# motor_driver_irf7413.net
KiCad netlist of a schematic drawn in EAGLE
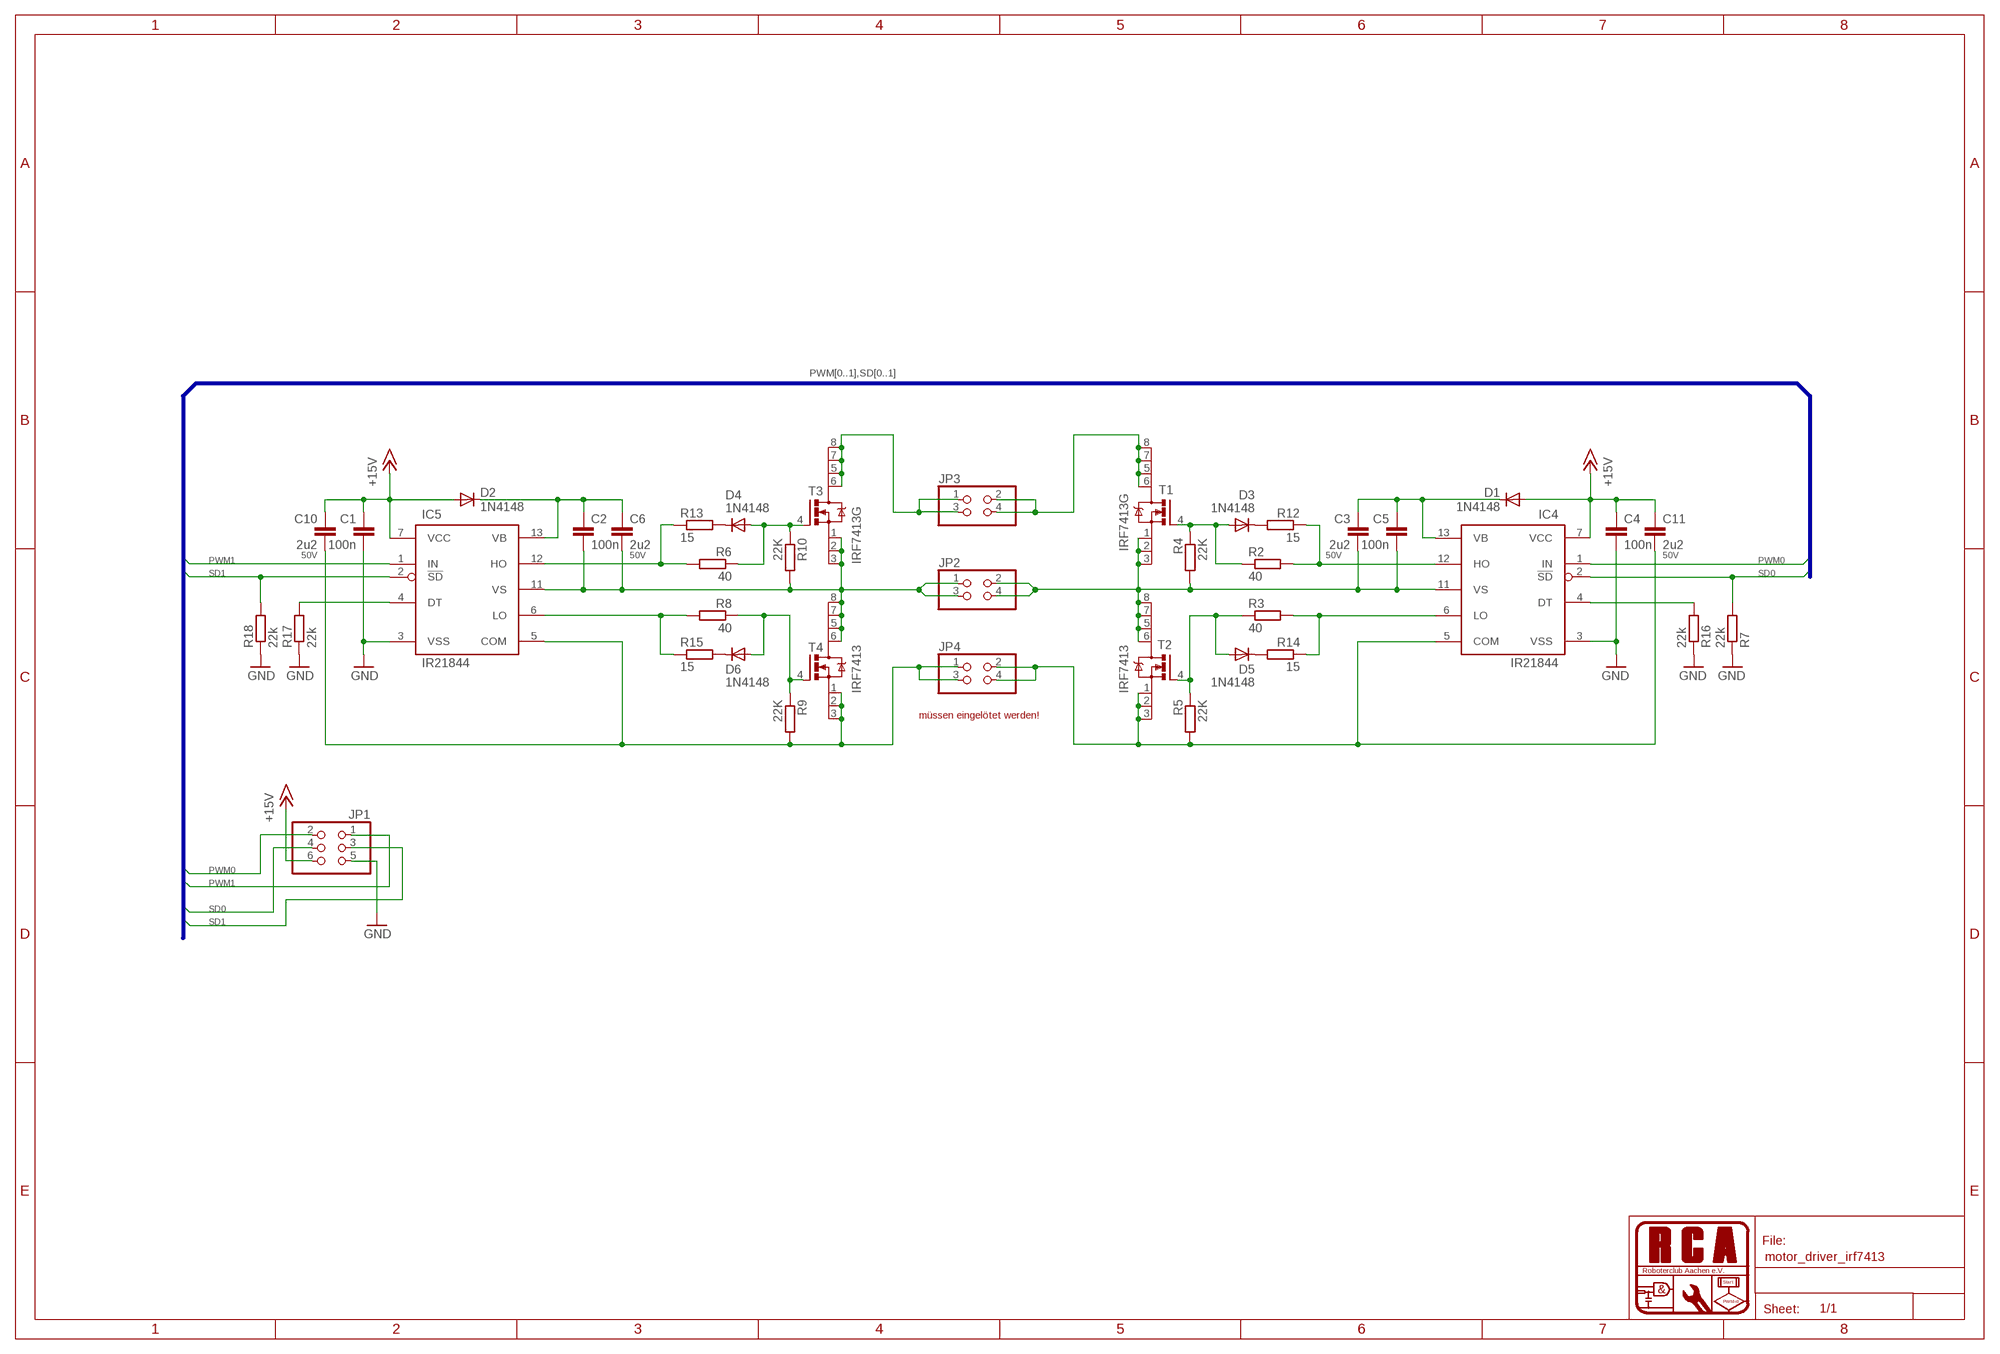
[diagram p0: schematic, sheet 1]

(export (version "E")
  (design (tool "Eeschema 10.0.6"))
  (components
    (comp (ref "C1")
      (value "100n")
      (footprint "eagle-import:C0805")
      (libsource (lib "eagle-import") (part "C-EUC0805"))
    )
    (comp (ref "C2")
      (value "100n")
      (footprint "eagle-import:C1206")
      (libsource (lib "eagle-import") (part "C-EUC1206"))
    )
    (comp (ref "C3")
      (value "2u2")
      (footprint "eagle-import:C1206")
      (fields (field (name "VOLTAGE") "50V"))
      (libsource (lib "eagle-import") (part "C-EUC1206"))
    )
    (comp (ref "C4")
      (value "100n")
      (footprint "eagle-import:C0805")
      (libsource (lib "eagle-import") (part "C-EUC0805"))
    )
    (comp (ref "C5")
      (value "100n")
      (footprint "eagle-import:C1206")
      (libsource (lib "eagle-import") (part "C-EUC1206"))
    )
    (comp (ref "C6")
      (value "2u2")
      (footprint "eagle-import:C1206")
      (fields (field (name "VOLTAGE") "50V"))
      (libsource (lib "eagle-import") (part "C-EUC1206"))
    )
    (comp (ref "C10")
      (value "2u2")
      (footprint "eagle-import:C1206")
      (fields (field (name "VOLTAGE") "50V"))
      (libsource (lib "eagle-import") (part "C-EUC1206"))
    )
    (comp (ref "C11")
      (value "2u2")
      (footprint "eagle-import:C1206")
      (fields (field (name "VOLTAGE") "50V"))
      (libsource (lib "eagle-import") (part "C-EUC1206"))
    )
    (comp (ref "D1")
      (value "1N4148")
      (footprint "eagle-import:SOD80C")
      (libsource (lib "eagle-import") (part "DIODE-SOD80C"))
    )
    (comp (ref "D2")
      (value "1N4148")
      (footprint "eagle-import:SOD80C")
      (libsource (lib "eagle-import") (part "DIODE-SOD80C"))
    )
    (comp (ref "D3")
      (value "1N4148")
      (footprint "eagle-import:SOD80C")
      (libsource (lib "eagle-import") (part "DIODE-SOD80C"))
    )
    (comp (ref "D4")
      (value "1N4148")
      (footprint "eagle-import:SOD80C")
      (libsource (lib "eagle-import") (part "DIODE-SOD80C"))
    )
    (comp (ref "D5")
      (value "1N4148")
      (footprint "eagle-import:SOD80C")
      (libsource (lib "eagle-import") (part "DIODE-SOD80C"))
    )
    (comp (ref "D6")
      (value "1N4148")
      (footprint "eagle-import:SOD80C")
      (libsource (lib "eagle-import") (part "DIODE-SOD80C"))
    )
    (comp (ref "IC4")
      (value "IR21844")
      (footprint "eagle-import:SO14")
      (libsource (lib "eagle-import") (part "IR21844"))
    )
    (comp (ref "IC5")
      (value "IR21844")
      (footprint "eagle-import:SO14")
      (libsource (lib "eagle-import") (part "IR21844"))
    )
    (comp (ref "JP1")
      (value "PINHD-2X3_2.54-SIDE")
      (footprint "eagle-import:2X03_SIDE")
      (libsource (lib "eagle-import") (part "PINHD-2X3_2.54-SIDE"))
    )
    (comp (ref "JP2")
      (value "PINHD-2X2_2.54-SIDE")
      (footprint "eagle-import:2X02_SIDE")
      (libsource (lib "eagle-import") (part "PINHD-2X2_2.54-SIDE"))
    )
    (comp (ref "JP3")
      (value "PINHD-2X2_2.54-SIDE")
      (footprint "eagle-import:2X02_SIDE")
      (libsource (lib "eagle-import") (part "PINHD-2X2_2.54-SIDE"))
    )
    (comp (ref "JP4")
      (value "PINHD-2X2_2.54-SIDE")
      (footprint "eagle-import:2X02_SIDE")
      (libsource (lib "eagle-import") (part "PINHD-2X2_2.54-SIDE"))
    )
    (comp (ref "R2")
      (value "40")
      (footprint "eagle-import:M0805")
      (libsource (lib "eagle-import") (part "R-EU_M0805"))
    )
    (comp (ref "R3")
      (value "40")
      (footprint "eagle-import:M0805")
      (libsource (lib "eagle-import") (part "R-EU_M0805"))
    )
    (comp (ref "R4")
      (value "22K")
      (footprint "eagle-import:M0805")
      (libsource (lib "eagle-import") (part "R-EU_M0805"))
    )
    (comp (ref "R5")
      (value "22K")
      (footprint "eagle-import:M0805")
      (libsource (lib "eagle-import") (part "R-EU_M0805"))
    )
    (comp (ref "R6")
      (value "40")
      (footprint "eagle-import:M0805")
      (libsource (lib "eagle-import") (part "R-EU_M0805"))
    )
    (comp (ref "R7")
      (value "22k")
      (footprint "eagle-import:M0805")
      (libsource (lib "eagle-import") (part "R-EU_M0805"))
    )
    (comp (ref "R8")
      (value "40")
      (footprint "eagle-import:M0805")
      (libsource (lib "eagle-import") (part "R-EU_M0805"))
    )
    (comp (ref "R9")
      (value "22K")
      (footprint "eagle-import:M0805")
      (libsource (lib "eagle-import") (part "R-EU_M0805"))
    )
    (comp (ref "R10")
      (value "22K")
      (footprint "eagle-import:M0805")
      (libsource (lib "eagle-import") (part "R-EU_M0805"))
    )
    (comp (ref "R12")
      (value "15")
      (footprint "eagle-import:M0805")
      (libsource (lib "eagle-import") (part "R-EU_M0805"))
    )
    (comp (ref "R13")
      (value "15")
      (footprint "eagle-import:M0805")
      (libsource (lib "eagle-import") (part "R-EU_M0805"))
    )
    (comp (ref "R14")
      (value "15")
      (footprint "eagle-import:M0805")
      (libsource (lib "eagle-import") (part "R-EU_M0805"))
    )
    (comp (ref "R15")
      (value "15")
      (footprint "eagle-import:M0805")
      (libsource (lib "eagle-import") (part "R-EU_M0805"))
    )
    (comp (ref "R16")
      (value "22k")
      (footprint "eagle-import:M0805")
      (libsource (lib "eagle-import") (part "R-EU_M0805"))
    )
    (comp (ref "R17")
      (value "22k")
      (footprint "eagle-import:M0805")
      (libsource (lib "eagle-import") (part "R-EU_M0805"))
    )
    (comp (ref "R18")
      (value "22k")
      (footprint "eagle-import:M0805")
      (libsource (lib "eagle-import") (part "R-EU_M0805"))
    )
    (comp (ref "T1")
      (value "IRF7413G")
      (footprint "eagle-import:SO08G")
      (libsource (lib "eagle-import") (part "IRF7413G"))
    )
    (comp (ref "T2")
      (value "IRF7413")
      (footprint "eagle-import:SO08")
      (libsource (lib "eagle-import") (part "IRF7413"))
    )
    (comp (ref "T3")
      (value "IRF7413G")
      (footprint "eagle-import:SO08G")
      (libsource (lib "eagle-import") (part "IRF7413G"))
    )
    (comp (ref "T4")
      (value "IRF7413")
      (footprint "eagle-import:SO08")
      (libsource (lib "eagle-import") (part "IRF7413"))
    )
  )
  (nets
    (net (code "1") (name "+15V") (class "Default")
      (node (ref "C1") (pin "1") (pinfunction "1_1") (pintype "passive"))
      (node (ref "C10") (pin "1") (pinfunction "1_1") (pintype "passive"))
      (node (ref "C11") (pin "1") (pinfunction "1_1") (pintype "passive"))
      (node (ref "C4") (pin "1") (pinfunction "1_1") (pintype "passive"))
      (node (ref "D1") (pin "A") (pinfunction "A_A") (pintype "passive"))
      (node (ref "D2") (pin "A") (pinfunction "A_A") (pintype "passive"))
      (node (ref "IC4") (pin "7") (pinfunction "VCC_7") (pintype "power_in"))
      (node (ref "IC5") (pin "7") (pinfunction "VCC_7") (pintype "power_in"))
      (node (ref "JP1") (pin "6") (pinfunction "6_6") (pintype "passive"))
    )
    (net (code "2") (name "/PWM0") (class "Default")
      (node (ref "IC4") (pin "1") (pinfunction "IN_1") (pintype "input"))
      (node (ref "JP1") (pin "2") (pinfunction "2_2") (pintype "passive"))
    )
    (net (code "3") (name "/PWM1") (class "Default")
      (node (ref "IC5") (pin "1") (pinfunction "IN_1") (pintype "input"))
      (node (ref "JP1") (pin "1") (pinfunction "1_1") (pintype "passive"))
    )
    (net (code "4") (name "/SD0") (class "Default")
      (node (ref "IC4") (pin "2") (pinfunction "~{SD}_2") (pintype "input"))
      (node (ref "JP1") (pin "4") (pinfunction "4_4") (pintype "passive"))
      (node (ref "R7") (pin "2") (pinfunction "2_2") (pintype "passive"))
    )
    (net (code "5") (name "/SD1") (class "Default")
      (node (ref "IC5") (pin "2") (pinfunction "~{SD}_2") (pintype "input"))
      (node (ref "JP1") (pin "3") (pinfunction "3_3") (pintype "passive"))
      (node (ref "R18") (pin "2") (pinfunction "2_2") (pintype "passive"))
    )
    (net (code "7") (name "GND") (class "Default")
      (node (ref "C1") (pin "2") (pinfunction "2_2") (pintype "passive"))
      (node (ref "C4") (pin "2") (pinfunction "2_2") (pintype "passive"))
      (node (ref "IC4") (pin "3") (pinfunction "VSS_3") (pintype "power_in"))
      (node (ref "IC5") (pin "3") (pinfunction "VSS_3") (pintype "power_in"))
      (node (ref "JP1") (pin "5") (pinfunction "5_5") (pintype "passive"))
      (node (ref "R16") (pin "1") (pinfunction "1_1") (pintype "passive"))
      (node (ref "R17") (pin "1") (pinfunction "1_1") (pintype "passive"))
      (node (ref "R18") (pin "1") (pinfunction "1_1") (pintype "passive"))
      (node (ref "R7") (pin "1") (pinfunction "1_1") (pintype "passive"))
    )
    (net (code "8") (name "Net-(D3-PadC)") (class "Default")
      (node (ref "D3") (pin "C") (pinfunction "C_C") (pintype "passive"))
      (node (ref "R12") (pin "2") (pinfunction "2_2") (pintype "passive"))
    )
    (net (code "9") (name "Net-(D4-PadC)") (class "Default")
      (node (ref "D4") (pin "C") (pinfunction "C_C") (pintype "passive"))
      (node (ref "R13") (pin "2") (pinfunction "2_2") (pintype "passive"))
    )
    (net (code "10") (name "Net-(D5-PadC)") (class "Default")
      (node (ref "D5") (pin "C") (pinfunction "C_C") (pintype "passive"))
      (node (ref "R14") (pin "2") (pinfunction "2_2") (pintype "passive"))
    )
    (net (code "11") (name "Net-(D6-PadC)") (class "Default")
      (node (ref "D6") (pin "C") (pinfunction "C_C") (pintype "passive"))
      (node (ref "R15") (pin "2") (pinfunction "2_2") (pintype "passive"))
    )
    (net (code "12") (name "Net-(IC4-COM)") (class "Default")
      (node (ref "C11") (pin "2") (pinfunction "2_2") (pintype "passive"))
      (node (ref "IC4") (pin "5") (pinfunction "COM_5") (pintype "power_in"))
      (node (ref "JP4") (pin "2") (pinfunction "2_2") (pintype "passive"))
      (node (ref "JP4") (pin "4") (pinfunction "4_4") (pintype "passive"))
      (node (ref "R5") (pin "2") (pinfunction "2_2") (pintype "passive"))
      (node (ref "T2") (pin "1") (pinfunction "S_1") (pintype "passive"))
      (node (ref "T2") (pin "2") (pinfunction "S1_2") (pintype "passive"))
      (node (ref "T2") (pin "3") (pinfunction "S2_3") (pintype "passive"))
    )
    (net (code "13") (name "Net-(IC4-DT)") (class "Default")
      (node (ref "IC4") (pin "4") (pinfunction "DT_4") (pintype "input"))
      (node (ref "R16") (pin "2") (pinfunction "2_2") (pintype "passive"))
    )
    (net (code "14") (name "Net-(IC4-HO)") (class "Default")
      (node (ref "IC4") (pin "12") (pinfunction "HO_12") (pintype "output"))
      (node (ref "R12") (pin "1") (pinfunction "1_1") (pintype "passive"))
      (node (ref "R2") (pin "2") (pinfunction "2_2") (pintype "passive"))
    )
    (net (code "15") (name "Net-(IC4-LO)") (class "Default")
      (node (ref "IC4") (pin "6") (pinfunction "LO_6") (pintype "output"))
      (node (ref "R14") (pin "1") (pinfunction "1_1") (pintype "passive"))
      (node (ref "R3") (pin "2") (pinfunction "2_2") (pintype "passive"))
    )
    (net (code "16") (name "Net-(IC4-VB)") (class "Default")
      (node (ref "C3") (pin "1") (pinfunction "1_1") (pintype "passive"))
      (node (ref "C5") (pin "1") (pinfunction "1_1") (pintype "passive"))
      (node (ref "D1") (pin "C") (pinfunction "C_C") (pintype "passive"))
      (node (ref "IC4") (pin "13") (pinfunction "VB_13") (pintype "power_in"))
    )
    (net (code "17") (name "Net-(IC4-VS)") (class "Default")
      (node (ref "C3") (pin "2") (pinfunction "2_2") (pintype "passive"))
      (node (ref "C5") (pin "2") (pinfunction "2_2") (pintype "passive"))
      (node (ref "IC4") (pin "11") (pinfunction "VS_11") (pintype "power_in"))
      (node (ref "JP2") (pin "2") (pinfunction "2_2") (pintype "passive"))
      (node (ref "JP2") (pin "4") (pinfunction "4_4") (pintype "passive"))
      (node (ref "R4") (pin "2") (pinfunction "2_2") (pintype "passive"))
      (node (ref "T1") (pin "1") (pinfunction "S_1") (pintype "passive"))
      (node (ref "T1") (pin "2") (pinfunction "S1_2") (pintype "passive"))
      (node (ref "T1") (pin "3") (pinfunction "S2_3") (pintype "passive"))
      (node (ref "T2") (pin "5") (pinfunction "D_5") (pintype "passive"))
      (node (ref "T2") (pin "6") (pinfunction "D1_6") (pintype "passive"))
      (node (ref "T2") (pin "7") (pinfunction "D2_7") (pintype "passive"))
      (node (ref "T2") (pin "8") (pinfunction "D3_8") (pintype "passive"))
    )
    (net (code "18") (name "Net-(IC5-COM)") (class "Default")
      (node (ref "C10") (pin "2") (pinfunction "2_2") (pintype "passive"))
      (node (ref "IC5") (pin "5") (pinfunction "COM_5") (pintype "power_in"))
      (node (ref "JP4") (pin "1") (pinfunction "1_1") (pintype "passive"))
      (node (ref "JP4") (pin "3") (pinfunction "3_3") (pintype "passive"))
      (node (ref "R9") (pin "2") (pinfunction "2_2") (pintype "passive"))
      (node (ref "T4") (pin "1") (pinfunction "S_1") (pintype "passive"))
      (node (ref "T4") (pin "2") (pinfunction "S1_2") (pintype "passive"))
      (node (ref "T4") (pin "3") (pinfunction "S2_3") (pintype "passive"))
    )
    (net (code "19") (name "Net-(IC5-DT)") (class "Default")
      (node (ref "IC5") (pin "4") (pinfunction "DT_4") (pintype "input"))
      (node (ref "R17") (pin "2") (pinfunction "2_2") (pintype "passive"))
    )
    (net (code "20") (name "Net-(IC5-HO)") (class "Default")
      (node (ref "IC5") (pin "12") (pinfunction "HO_12") (pintype "output"))
      (node (ref "R13") (pin "1") (pinfunction "1_1") (pintype "passive"))
      (node (ref "R6") (pin "2") (pinfunction "2_2") (pintype "passive"))
    )
    (net (code "21") (name "Net-(IC5-LO)") (class "Default")
      (node (ref "IC5") (pin "6") (pinfunction "LO_6") (pintype "output"))
      (node (ref "R15") (pin "1") (pinfunction "1_1") (pintype "passive"))
      (node (ref "R8") (pin "2") (pinfunction "2_2") (pintype "passive"))
    )
    (net (code "22") (name "Net-(IC5-VB)") (class "Default")
      (node (ref "C2") (pin "1") (pinfunction "1_1") (pintype "passive"))
      (node (ref "C6") (pin "1") (pinfunction "1_1") (pintype "passive"))
      (node (ref "D2") (pin "C") (pinfunction "C_C") (pintype "passive"))
      (node (ref "IC5") (pin "13") (pinfunction "VB_13") (pintype "power_in"))
    )
    (net (code "23") (name "Net-(IC5-VS)") (class "Default")
      (node (ref "C2") (pin "2") (pinfunction "2_2") (pintype "passive"))
      (node (ref "C6") (pin "2") (pinfunction "2_2") (pintype "passive"))
      (node (ref "IC5") (pin "11") (pinfunction "VS_11") (pintype "power_in"))
      (node (ref "JP2") (pin "1") (pinfunction "1_1") (pintype "passive"))
      (node (ref "JP2") (pin "3") (pinfunction "3_3") (pintype "passive"))
      (node (ref "R10") (pin "2") (pinfunction "2_2") (pintype "passive"))
      (node (ref "T3") (pin "1") (pinfunction "S_1") (pintype "passive"))
      (node (ref "T3") (pin "2") (pinfunction "S1_2") (pintype "passive"))
      (node (ref "T3") (pin "3") (pinfunction "S2_3") (pintype "passive"))
      (node (ref "T4") (pin "5") (pinfunction "D_5") (pintype "passive"))
      (node (ref "T4") (pin "6") (pinfunction "D1_6") (pintype "passive"))
      (node (ref "T4") (pin "7") (pinfunction "D2_7") (pintype "passive"))
      (node (ref "T4") (pin "8") (pinfunction "D3_8") (pintype "passive"))
    )
    (net (code "24") (name "Net-(T1-D)") (class "Default")
      (node (ref "JP3") (pin "2") (pinfunction "2_2") (pintype "passive"))
      (node (ref "JP3") (pin "4") (pinfunction "4_4") (pintype "passive"))
      (node (ref "T1") (pin "5") (pinfunction "D_5") (pintype "passive"))
      (node (ref "T1") (pin "6") (pinfunction "D1_6") (pintype "passive"))
      (node (ref "T1") (pin "7") (pinfunction "D2_7") (pintype "passive"))
      (node (ref "T1") (pin "8") (pinfunction "D3_8") (pintype "passive"))
    )
    (net (code "25") (name "Net-(T1-G)") (class "Default")
      (node (ref "D3") (pin "A") (pinfunction "A_A") (pintype "passive"))
      (node (ref "R2") (pin "1") (pinfunction "1_1") (pintype "passive"))
      (node (ref "R4") (pin "1") (pinfunction "1_1") (pintype "passive"))
      (node (ref "T1") (pin "4") (pinfunction "G_4") (pintype "passive"))
    )
    (net (code "26") (name "Net-(T2-G)") (class "Default")
      (node (ref "D5") (pin "A") (pinfunction "A_A") (pintype "passive"))
      (node (ref "R3") (pin "1") (pinfunction "1_1") (pintype "passive"))
      (node (ref "R5") (pin "1") (pinfunction "1_1") (pintype "passive"))
      (node (ref "T2") (pin "4") (pinfunction "G_4") (pintype "passive"))
    )
    (net (code "27") (name "Net-(T3-D)") (class "Default")
      (node (ref "JP3") (pin "1") (pinfunction "1_1") (pintype "passive"))
      (node (ref "JP3") (pin "3") (pinfunction "3_3") (pintype "passive"))
      (node (ref "T3") (pin "5") (pinfunction "D_5") (pintype "passive"))
      (node (ref "T3") (pin "6") (pinfunction "D1_6") (pintype "passive"))
      (node (ref "T3") (pin "7") (pinfunction "D2_7") (pintype "passive"))
      (node (ref "T3") (pin "8") (pinfunction "D3_8") (pintype "passive"))
    )
    (net (code "28") (name "Net-(T3-G)") (class "Default")
      (node (ref "D4") (pin "A") (pinfunction "A_A") (pintype "passive"))
      (node (ref "R10") (pin "1") (pinfunction "1_1") (pintype "passive"))
      (node (ref "R6") (pin "1") (pinfunction "1_1") (pintype "passive"))
      (node (ref "T3") (pin "4") (pinfunction "G_4") (pintype "passive"))
    )
    (net (code "29") (name "Net-(T4-G)") (class "Default")
      (node (ref "D6") (pin "A") (pinfunction "A_A") (pintype "passive"))
      (node (ref "R8") (pin "1") (pinfunction "1_1") (pintype "passive"))
      (node (ref "R9") (pin "1") (pinfunction "1_1") (pintype "passive"))
      (node (ref "T4") (pin "4") (pinfunction "G_4") (pintype "passive"))
    )
  )
)
